# Brightness_Sensor_Schematic.net
KiCad netlist of a schematic drawn in Altium Designer
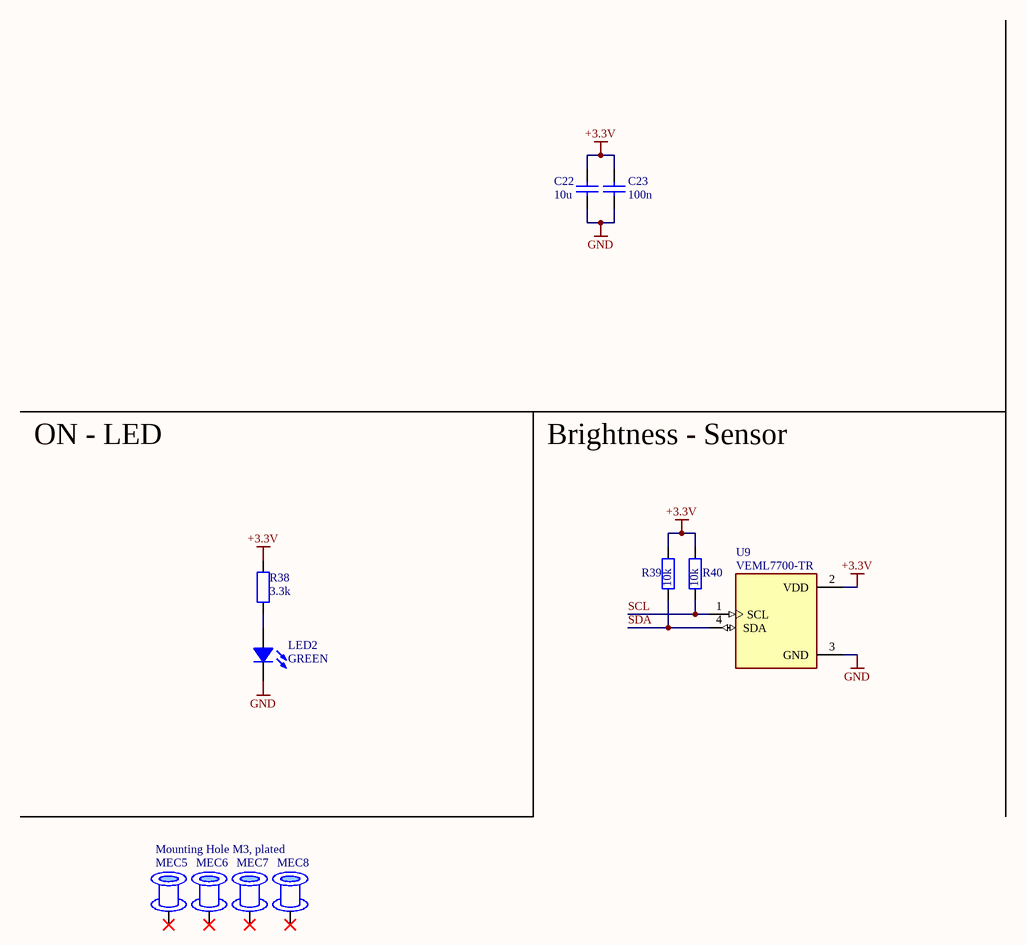
[diagram p0: Brightness_Sensor_Schematic.SchDoc]

(export (version "E")
  (design (tool "Eeschema 10.0.6"))
  (components
    (comp (ref "C22")
      (value "10u")
      (footprint "PCB_Altium_Library_Manuel:0603_CAPACITOR")
      (description "0603")
      (libsource (lib "Schematic_Altium_Library_Manuel") (part "Capacitor"))
    )
    (comp (ref "C23")
      (value "100n")
      (footprint "PCB_Altium_Library_Manuel:0603_CAPACITOR")
      (description "0603")
      (libsource (lib "Schematic_Altium_Library_Manuel") (part "Capacitor"))
    )
    (comp (ref "LED2")
      (value "GREEN")
      (footprint "PCB_Altium_Library_Manuel:LED_0603, GREEN")
      (description "LED 0603, Green, 3.2 V, 20 mA, 430 mcd")
      (libsource (lib "Schematic_Altium_Library_Manuel") (part "LED_0603, GREEN"))
    )
    (comp (ref "MEC5")
      (value "Mounting Hole M3, plated")
      (footprint "PCB_Altium_Library_Manuel:Mounting Hole M3, plated")
      (description "Mounting Hole for M3 Screw, plated to connect signal")
      (libsource (lib "Schematic_Altium_Library_Manuel") (part "Mounting Hole M3, plated"))
    )
    (comp (ref "MEC6")
      (value "Mounting Hole M3, plated")
      (footprint "PCB_Altium_Library_Manuel:Mounting Hole M3, plated")
      (description "Mounting Hole for M3 Screw, plated to connect signal")
      (libsource (lib "Schematic_Altium_Library_Manuel") (part "Mounting Hole M3, plated"))
    )
    (comp (ref "MEC7")
      (value "Mounting Hole M3, plated")
      (footprint "PCB_Altium_Library_Manuel:Mounting Hole M3, plated")
      (description "Mounting Hole for M3 Screw, plated to connect signal")
      (libsource (lib "Schematic_Altium_Library_Manuel") (part "Mounting Hole M3, plated"))
    )
    (comp (ref "MEC8")
      (value "Mounting Hole M3, plated")
      (footprint "PCB_Altium_Library_Manuel:Mounting Hole M3, plated")
      (description "Mounting Hole for M3 Screw, plated to connect signal")
      (libsource (lib "Schematic_Altium_Library_Manuel") (part "Mounting Hole M3, plated"))
    )
    (comp (ref "R38")
      (value "3.3k")
      (footprint "PCB_Altium_Library_Manuel:0603_Resistor")
      (description "0603")
      (libsource (lib "Schematic_Altium_Library_Manuel") (part "Resistor"))
    )
    (comp (ref "R39")
      (value "10k")
      (footprint "PCB_Altium_Library_Manuel:0603_Resistor")
      (description "0603")
      (libsource (lib "Schematic_Altium_Library_Manuel") (part "Resistor"))
    )
    (comp (ref "R40")
      (value "10k")
      (footprint "PCB_Altium_Library_Manuel:0603_Resistor")
      (description "0603")
      (libsource (lib "Schematic_Altium_Library_Manuel") (part "Resistor"))
    )
    (comp (ref "U9")
      (value "VEML7700-TR")
      (footprint "PCB_Altium_Library_Manuel:Brightness_Sensor")
      (description "SENSOR OPT 545NMAMB 4 SMD J LEAD.")
      (libsource (lib "Schematic_Altium_Library_Manuel") (part "Brightness_Sensor"))
    )
  )
  (nets
    (net (code "1") (name "+3.3V") (class "Default")
      (node (ref "C22") (pin "2") (pinfunction "2_2") (pintype "passive"))
      (node (ref "C23") (pin "2") (pinfunction "2_2") (pintype "passive"))
      (node (ref "R38") (pin "2") (pinfunction "2_2") (pintype "passive"))
      (node (ref "R39") (pin "2") (pinfunction "2_2") (pintype "passive"))
      (node (ref "R40") (pin "2") (pinfunction "2_2") (pintype "passive"))
      (node (ref "U9") (pin "2") (pinfunction "VDD_2") (pintype "power_in"))
    )
    (net (code "2") (name "/SCL") (class "Default")
      (node (ref "R40") (pin "1") (pinfunction "1_1") (pintype "passive"))
      (node (ref "U9") (pin "1") (pinfunction "SCL_1") (pintype "input"))
    )
    (net (code "3") (name "/SDA") (class "Default")
      (node (ref "R39") (pin "1") (pinfunction "1_1") (pintype "passive"))
      (node (ref "U9") (pin "4") (pinfunction "SDA_4") (pintype "bidirectional"))
    )
    (net (code "4") (name "GND") (class "Default")
      (node (ref "C22") (pin "1") (pinfunction "1_1") (pintype "passive"))
      (node (ref "C23") (pin "1") (pinfunction "1_1") (pintype "passive"))
      (node (ref "LED2") (pin "K") (pinfunction "K_K") (pintype "passive"))
      (node (ref "U9") (pin "3") (pinfunction "GND_3") (pintype "power_in"))
    )
    (net (code "5") (name "Net-(LED2-PadA)") (class "Default")
      (node (ref "LED2") (pin "A") (pinfunction "A_A") (pintype "passive"))
      (node (ref "R38") (pin "1") (pinfunction "1_1") (pintype "passive"))
    )
    (net (code "6") (name "unconnected-(MEC5-Pad1)") (class "Default")
      (node (ref "MEC5") (pin "1") (pinfunction "1_1") (pintype "passive+no_connect"))
    )
    (net (code "7") (name "unconnected-(MEC6-Pad1)") (class "Default")
      (node (ref "MEC6") (pin "1") (pinfunction "1_1") (pintype "passive+no_connect"))
    )
    (net (code "8") (name "unconnected-(MEC7-Pad1)") (class "Default")
      (node (ref "MEC7") (pin "1") (pinfunction "1_1") (pintype "passive+no_connect"))
    )
    (net (code "9") (name "unconnected-(MEC8-Pad1)") (class "Default")
      (node (ref "MEC8") (pin "1") (pinfunction "1_1") (pintype "passive+no_connect"))
    )
  )
)
